# PCB.net
KiCad netlist of a schematic drawn in Altium Designer
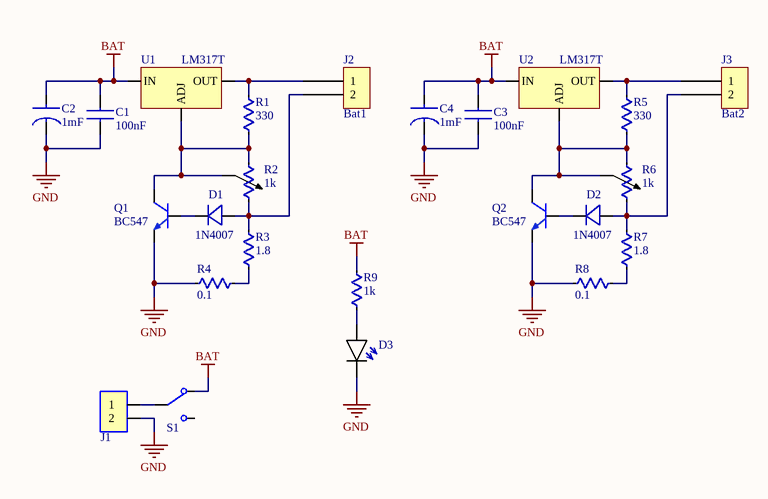
[diagram p0: PCB.SchDoc]

(export (version "E")
  (design (tool "Eeschema 10.0.6"))
  (components
    (comp (ref "C1")
      (value "100nF")
      (footprint "CAP-CER")
      (fields (field (name "Comment") "CAP-CER"))
      (libsource (lib "AltiumLibrary") (part "CAP-CER"))
    )
    (comp (ref "C2")
      (value "1mF")
      (footprint "CAP-ELEC-5x11x2mm")
      (fields (field (name "Comment") "CAP-ELEC"))
      (libsource (lib "AltiumLibrary") (part "CAP-ELEC"))
    )
    (comp (ref "C3")
      (value "100nF")
      (footprint "CAP-CER")
      (fields (field (name "Comment") "CAP-CER"))
      (libsource (lib "AltiumLibrary") (part "CAP-CER"))
    )
    (comp (ref "C4")
      (value "1mF")
      (footprint "CAP-ELEC-5x11x2mm")
      (fields (field (name "Comment") "CAP-ELEC"))
      (libsource (lib "AltiumLibrary") (part "CAP-ELEC"))
    )
    (comp (ref "D1")
      (value "1N4007")
      (footprint "DO-41 VERTICAL")
      (libsource (lib "AltiumLibrary") (part "DIODE"))
    )
    (comp (ref "D2")
      (value "1N4007")
      (footprint "DO-41 VERTICAL")
      (libsource (lib "AltiumLibrary") (part "DIODE"))
    )
    (comp (ref "D3") (value "LED") (footprint "LED-3MM-RED") (libsource (lib "AltiumLibrary") (part "LED")))
    (comp (ref "J1")
      (value "2-BLOCK_TERMINAL")
      (footprint "BLOCK_TERMINAL-2")
      (libsource (lib "AltiumLibrary") (part "2-BLOCK_TERMINAL"))
    )
    (comp (ref "J2")
      (value "Bat1")
      (footprint "HEADER 1x2")
      (libsource (lib "AltiumLibrary") (part "Header 1x2"))
    )
    (comp (ref "J3")
      (value "Bat2")
      (footprint "HEADER 1x2")
      (libsource (lib "AltiumLibrary") (part "Header 1x2"))
    )
    (comp (ref "Q1") (value "BC547") (footprint "TO-92") (libsource (lib "AltiumLibrary") (part "NPN")))
    (comp (ref "Q2") (value "BC547") (footprint "TO-92") (libsource (lib "AltiumLibrary") (part "NPN")))
    (comp (ref "R1")
      (value "330")
      (footprint "RES VERTICAL")
      (fields (field (name "Comment") "RES"))
      (libsource (lib "AltiumLibrary") (part "RES"))
    )
    (comp (ref "R2")
      (value "1k")
      (footprint "TRIMPOT")
      (fields (field (name "Comment") "POT"))
      (libsource (lib "AltiumLibrary") (part "POT"))
    )
    (comp (ref "R3")
      (value "1.8")
      (footprint "RES VERTICAL")
      (fields (field (name "Comment") "RES"))
      (libsource (lib "AltiumLibrary") (part "RES"))
    )
    (comp (ref "R4")
      (value "0.1")
      (footprint "RES-Axial-400mil")
      (fields (field (name "Comment") "RES"))
      (libsource (lib "") (part "RES_1"))
    )
    (comp (ref "R5")
      (value "330")
      (footprint "RES VERTICAL")
      (fields (field (name "Comment") "RES"))
      (libsource (lib "AltiumLibrary") (part "RES"))
    )
    (comp (ref "R6")
      (value "1k")
      (footprint "TRIMPOT")
      (fields (field (name "Comment") "POT"))
      (libsource (lib "AltiumLibrary") (part "POT"))
    )
    (comp (ref "R7")
      (value "1.8")
      (footprint "RES VERTICAL")
      (fields (field (name "Comment") "RES"))
      (libsource (lib "AltiumLibrary") (part "RES"))
    )
    (comp (ref "R8")
      (value "0.1")
      (footprint "RES-Axial-400mil")
      (fields (field (name "Comment") "RES"))
      (libsource (lib "") (part "RES_1"))
    )
    (comp (ref "R9")
      (value "1k")
      (footprint "RES VERTICAL")
      (fields (field (name "Comment") "RES"))
      (libsource (lib "AltiumLibrary") (part "RES"))
    )
    (comp (ref "S1")
      (value "SLIDE-SWITCH")
      (footprint "SWITCH")
      (libsource (lib "AltiumLibrary") (part "SLIDE-SWITCH"))
    )
    (comp (ref "U1") (value "LM317T") (footprint "TO-220") (libsource (lib "AltiumLibrary") (part "LM317")))
    (comp (ref "U2") (value "LM317T") (footprint "TO-220") (libsource (lib "AltiumLibrary") (part "LM317")))
  )
  (nets
    (net (code "1") (name "BAT") (class "Default")
      (node (ref "C1") (pin "2") (pintype "passive"))
      (node (ref "C2") (pin "1") (pintype "passive"))
      (node (ref "C3") (pin "2") (pintype "passive"))
      (node (ref "C4") (pin "1") (pintype "passive"))
      (node (ref "R9") (pin "2") (pintype "passive"))
      (node (ref "S1") (pin "1") (pintype "power_in"))
      (node (ref "U1") (pin "1") (pinfunction "IN_1") (pintype "power_in"))
      (node (ref "U2") (pin "1") (pinfunction "IN_1") (pintype "power_in"))
    )
    (net (code "2") (name "GND") (class "Default")
      (node (ref "C1") (pin "1") (pintype "passive"))
      (node (ref "C2") (pin "2") (pintype "passive"))
      (node (ref "C3") (pin "1") (pintype "passive"))
      (node (ref "C4") (pin "2") (pintype "passive"))
      (node (ref "D3") (pin "K") (pintype "passive"))
      (node (ref "J1") (pin "2") (pinfunction "2_2") (pintype "passive"))
      (node (ref "Q1") (pin "E") (pinfunction "E_E") (pintype "passive"))
      (node (ref "Q2") (pin "E") (pinfunction "E_E") (pintype "passive"))
      (node (ref "R4") (pin "1") (pintype "passive"))
      (node (ref "R8") (pin "1") (pintype "passive"))
    )
    (net (code "3") (name "Net-(D1-PadA)") (class "Default")
      (node (ref "D1") (pin "A") (pintype "passive"))
      (node (ref "J2") (pin "2") (pinfunction "2_2") (pintype "passive"))
      (node (ref "R2") (pin "1") (pintype "passive"))
      (node (ref "R3") (pin "2") (pintype "passive"))
    )
    (net (code "4") (name "Net-(D1-PadK)") (class "Default")
      (node (ref "D1") (pin "K") (pintype "passive"))
      (node (ref "Q1") (pin "B") (pinfunction "B_B") (pintype "passive"))
    )
    (net (code "5") (name "Net-(D2-PadA)") (class "Default")
      (node (ref "D2") (pin "A") (pintype "passive"))
      (node (ref "J3") (pin "2") (pinfunction "2_2") (pintype "passive"))
      (node (ref "R6") (pin "1") (pintype "passive"))
      (node (ref "R7") (pin "2") (pintype "passive"))
    )
    (net (code "6") (name "Net-(D2-PadK)") (class "Default")
      (node (ref "D2") (pin "K") (pintype "passive"))
      (node (ref "Q2") (pin "B") (pinfunction "B_B") (pintype "passive"))
    )
    (net (code "7") (name "Net-(D3-PadA)") (class "Default")
      (node (ref "D3") (pin "A") (pintype "passive"))
      (node (ref "R9") (pin "1") (pintype "passive"))
    )
    (net (code "8") (name "Net-(J1-Pad1)") (class "Default")
      (node (ref "J1") (pin "1") (pinfunction "1_1") (pintype "passive"))
      (node (ref "S1") (pin "2") (pintype "power_in"))
    )
    (net (code "9") (name "Net-(R3-Pad1)") (class "Default")
      (node (ref "R3") (pin "1") (pintype "passive"))
      (node (ref "R4") (pin "2") (pintype "passive"))
    )
    (net (code "10") (name "Net-(R7-Pad1)") (class "Default")
      (node (ref "R7") (pin "1") (pintype "passive"))
      (node (ref "R8") (pin "2") (pintype "passive"))
    )
    (net (code "11") (name "Net-(U1-ADJ)") (class "Default")
      (node (ref "Q1") (pin "C") (pinfunction "C_C") (pintype "passive"))
      (node (ref "R1") (pin "1") (pintype "passive"))
      (node (ref "R2") (pin "2") (pintype "passive"))
      (node (ref "R2") (pin "3") (pintype "passive"))
      (node (ref "U1") (pin "2") (pinfunction "ADJ_2") (pintype "power_in"))
    )
    (net (code "12") (name "Net-(U1-OUT)") (class "Default")
      (node (ref "J2") (pin "1") (pinfunction "1_1") (pintype "passive"))
      (node (ref "R1") (pin "2") (pintype "passive"))
      (node (ref "U1") (pin "3") (pinfunction "OUT_3") (pintype "power_in"))
    )
    (net (code "13") (name "Net-(U2-ADJ)") (class "Default")
      (node (ref "Q2") (pin "C") (pinfunction "C_C") (pintype "passive"))
      (node (ref "R5") (pin "1") (pintype "passive"))
      (node (ref "R6") (pin "2") (pintype "passive"))
      (node (ref "R6") (pin "3") (pintype "passive"))
      (node (ref "U2") (pin "2") (pinfunction "ADJ_2") (pintype "power_in"))
    )
    (net (code "14") (name "Net-(U2-OUT)") (class "Default")
      (node (ref "J3") (pin "1") (pinfunction "1_1") (pintype "passive"))
      (node (ref "R5") (pin "2") (pintype "passive"))
      (node (ref "U2") (pin "3") (pinfunction "OUT_3") (pintype "power_in"))
    )
    (net (code "15") (name "unconnected-(S1-Pad3)") (class "Default")
      (node (ref "S1") (pin "3") (pintype "power_in"))
    )
  )
)
